# Esquematico.net
KiCad netlist of a schematic drawn in Altium Designer
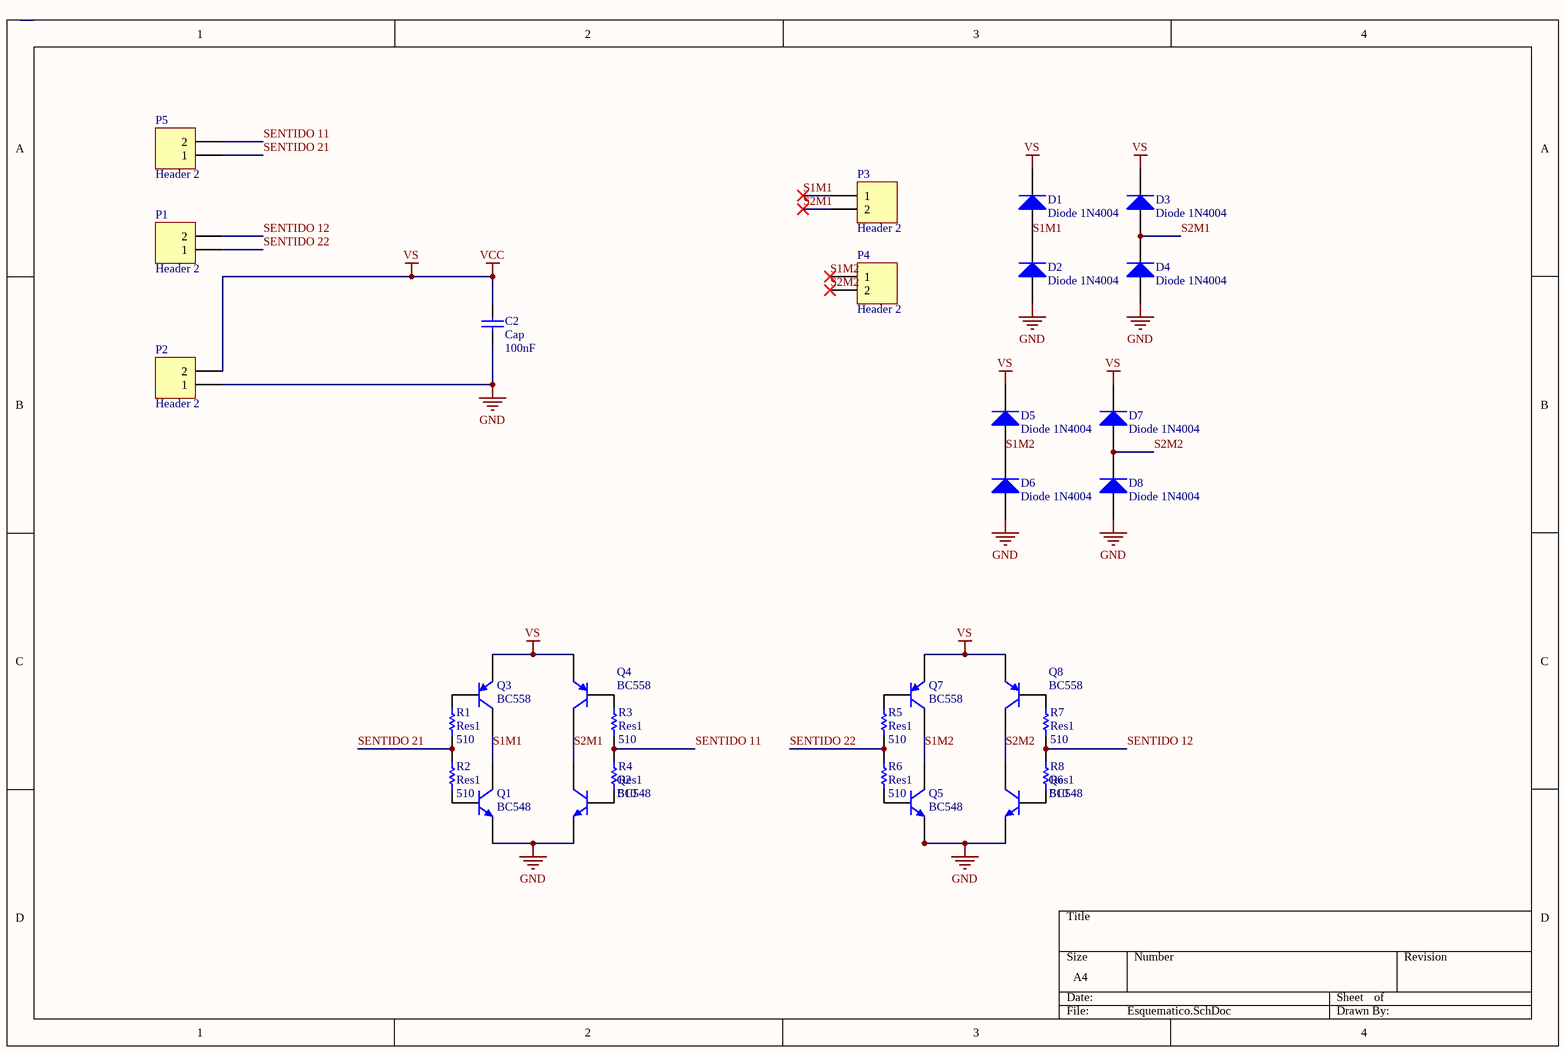
[diagram p0: Esquematico.SchDoc]

(export (version "E")
  (design (tool "Eeschema 10.0.6"))
  (components
    (comp (ref "C2")
      (value "Cap")
      (footprint "RAD-0.1")
      (description "Capacitor")
      (fields (field (name "ALTIUM_VALUE") "100nF") (field (name "PUBLISHER") "Altium Limited"))
      (libsource (lib "Miscellaneous Devices") (part "Cap"))
    )
    (comp (ref "D1")
      (value "Diode 1N4004")
      (footprint "DO-41")
      (description "1 Amp General Purpose Rectifier")
      (fields (field (name "PUBLISHER") "Altium Limited"))
      (libsource (lib "Miscellaneous Devices") (part "Diode 1N4004"))
    )
    (comp (ref "D2")
      (value "Diode 1N4004")
      (footprint "DO-41")
      (description "1 Amp General Purpose Rectifier")
      (fields (field (name "PUBLISHER") "Altium Limited"))
      (libsource (lib "Miscellaneous Devices") (part "Diode 1N4004"))
    )
    (comp (ref "D3")
      (value "Diode 1N4004")
      (footprint "DO-41")
      (description "1 Amp General Purpose Rectifier")
      (fields (field (name "PUBLISHER") "Altium Limited"))
      (libsource (lib "Miscellaneous Devices") (part "Diode 1N4004"))
    )
    (comp (ref "D4")
      (value "Diode 1N4004")
      (footprint "DO-41")
      (description "1 Amp General Purpose Rectifier")
      (fields (field (name "PUBLISHER") "Altium Limited"))
      (libsource (lib "Miscellaneous Devices") (part "Diode 1N4004"))
    )
    (comp (ref "D5")
      (value "Diode 1N4004")
      (footprint "DO-41")
      (description "1 Amp General Purpose Rectifier")
      (fields (field (name "PUBLISHER") "Altium Limited"))
      (libsource (lib "Miscellaneous Devices") (part "Diode 1N4004"))
    )
    (comp (ref "D6")
      (value "Diode 1N4004")
      (footprint "DO-41")
      (description "1 Amp General Purpose Rectifier")
      (fields (field (name "PUBLISHER") "Altium Limited"))
      (libsource (lib "Miscellaneous Devices") (part "Diode 1N4004"))
    )
    (comp (ref "D7")
      (value "Diode 1N4004")
      (footprint "DO-41")
      (description "1 Amp General Purpose Rectifier")
      (fields (field (name "PUBLISHER") "Altium Limited"))
      (libsource (lib "Miscellaneous Devices") (part "Diode 1N4004"))
    )
    (comp (ref "D8")
      (value "Diode 1N4004")
      (footprint "DO-41")
      (description "1 Amp General Purpose Rectifier")
      (fields (field (name "PUBLISHER") "Altium Limited"))
      (libsource (lib "Miscellaneous Devices") (part "Diode 1N4004"))
    )
    (comp (ref "P1")
      (value "Header 2")
      (footprint "HDR1X2")
      (description "Header, 2-Pin")
      (fields (field (name "PUBLISHER") "Altium Limited"))
      (libsource (lib "Miscellaneous Connectors") (part "Header 2"))
    )
    (comp (ref "P2")
      (value "Header 2")
      (footprint "HDR1X2")
      (description "Header, 2-Pin")
      (fields (field (name "PUBLISHER") "Altium Limited"))
      (libsource (lib "Miscellaneous Connectors") (part "Header 2"))
    )
    (comp (ref "P3")
      (value "Header 2")
      (footprint "HDR1X2")
      (description "Header, 2-Pin")
      (fields (field (name "PUBLISHER") "Altium Limited"))
      (libsource (lib "") (part "Header 2_1"))
    )
    (comp (ref "P4")
      (value "Header 2")
      (footprint "HDR1X2")
      (description "Header, 2-Pin")
      (fields (field (name "PUBLISHER") "Altium Limited"))
      (libsource (lib "") (part "Header 2_1"))
    )
    (comp (ref "P5")
      (value "Header 2")
      (footprint "HDR1X2")
      (description "Header, 2-Pin")
      (fields (field (name "PUBLISHER") "Altium Limited"))
      (libsource (lib "Miscellaneous Connectors") (part "Header 2"))
    )
    (comp (ref "Q1")
      (value "BC548")
      (footprint "TO-92")
      (description "NPN General Purpose Amplifier")
      (fields (field (name "PUBLISHER") "Altium Limited"))
      (libsource (lib "Components") (part "BC548"))
    )
    (comp (ref "Q2")
      (value "BC548")
      (footprint "TO-92")
      (description "NPN General Purpose Amplifier")
      (fields (field (name "PUBLISHER") "Altium Limited"))
      (libsource (lib "Components") (part "BC548"))
    )
    (comp (ref "Q3")
      (value "BC558")
      (footprint "TO-92")
      (description "PNP Bipolar Transistor")
      (fields (field (name "PUBLISHER") "Altium Limited"))
      (libsource (lib "Components") (part "BC558"))
    )
    (comp (ref "Q4")
      (value "BC558")
      (footprint "TO-92")
      (description "PNP Bipolar Transistor")
      (fields (field (name "PUBLISHER") "Altium Limited"))
      (libsource (lib "Components") (part "BC558"))
    )
    (comp (ref "Q5")
      (value "BC548")
      (footprint "TO-92")
      (description "NPN General Purpose Amplifier")
      (fields (field (name "PUBLISHER") "Altium Limited"))
      (libsource (lib "Components") (part "BC548"))
    )
    (comp (ref "Q6")
      (value "BC548")
      (footprint "TO-92")
      (description "NPN General Purpose Amplifier")
      (fields (field (name "PUBLISHER") "Altium Limited"))
      (libsource (lib "Components") (part "BC548"))
    )
    (comp (ref "Q7")
      (value "BC558")
      (footprint "TO-92")
      (description "PNP Bipolar Transistor")
      (fields (field (name "PUBLISHER") "Altium Limited"))
      (libsource (lib "Components") (part "BC558"))
    )
    (comp (ref "Q8")
      (value "BC558")
      (footprint "TO-92")
      (description "PNP Bipolar Transistor")
      (fields (field (name "PUBLISHER") "Altium Limited"))
      (libsource (lib "Components") (part "BC558"))
    )
    (comp (ref "R1")
      (value "Res1")
      (footprint "AXIAL-0.3")
      (description "Resistor")
      (fields (field (name "ALTIUM_VALUE") "510") (field (name "PUBLISHER") "Altium Limited"))
      (libsource (lib "Miscellaneous Devices") (part "Res1"))
    )
    (comp (ref "R2")
      (value "Res1")
      (footprint "AXIAL-0.3")
      (description "Resistor")
      (fields (field (name "ALTIUM_VALUE") "510") (field (name "PUBLISHER") "Altium Limited"))
      (libsource (lib "Miscellaneous Devices") (part "Res1"))
    )
    (comp (ref "R3")
      (value "Res1")
      (footprint "AXIAL-0.3")
      (description "Resistor")
      (fields (field (name "ALTIUM_VALUE") "510") (field (name "PUBLISHER") "Altium Limited"))
      (libsource (lib "Miscellaneous Devices") (part "Res1"))
    )
    (comp (ref "R4")
      (value "Res1")
      (footprint "AXIAL-0.3")
      (description "Resistor")
      (fields (field (name "ALTIUM_VALUE") "510") (field (name "PUBLISHER") "Altium Limited"))
      (libsource (lib "Miscellaneous Devices") (part "Res1"))
    )
    (comp (ref "R5")
      (value "Res1")
      (footprint "AXIAL-0.3")
      (description "Resistor")
      (fields (field (name "ALTIUM_VALUE") "510") (field (name "PUBLISHER") "Altium Limited"))
      (libsource (lib "Miscellaneous Devices") (part "Res1"))
    )
    (comp (ref "R6")
      (value "Res1")
      (footprint "AXIAL-0.3")
      (description "Resistor")
      (fields (field (name "ALTIUM_VALUE") "510") (field (name "PUBLISHER") "Altium Limited"))
      (libsource (lib "Miscellaneous Devices") (part "Res1"))
    )
    (comp (ref "R7")
      (value "Res1")
      (footprint "AXIAL-0.3")
      (description "Resistor")
      (fields (field (name "ALTIUM_VALUE") "510") (field (name "PUBLISHER") "Altium Limited"))
      (libsource (lib "Miscellaneous Devices") (part "Res1"))
    )
    (comp (ref "R8")
      (value "Res1")
      (footprint "AXIAL-0.3")
      (description "Resistor")
      (fields (field (name "ALTIUM_VALUE") "510") (field (name "PUBLISHER") "Altium Limited"))
      (libsource (lib "Miscellaneous Devices") (part "Res1"))
    )
  )
  (nets
    (net (code "1") (name "/S1M1") (class "Default")
      (node (ref "D1") (pin "1") (pinfunction "A_1") (pintype "passive"))
      (node (ref "D2") (pin "2") (pinfunction "K_2") (pintype "passive"))
      (node (ref "P3") (pin "1") (pinfunction "1_1") (pintype "passive"))
      (node (ref "Q1") (pin "3") (pinfunction "C_3") (pintype "passive"))
      (node (ref "Q3") (pin "3") (pinfunction "C_3") (pintype "passive"))
    )
    (net (code "2") (name "/S1M2") (class "Default")
      (node (ref "D5") (pin "1") (pinfunction "A_1") (pintype "passive"))
      (node (ref "D6") (pin "2") (pinfunction "K_2") (pintype "passive"))
      (node (ref "P4") (pin "1") (pinfunction "1_1") (pintype "passive"))
      (node (ref "Q5") (pin "3") (pinfunction "C_3") (pintype "passive"))
      (node (ref "Q7") (pin "3") (pinfunction "C_3") (pintype "passive"))
    )
    (net (code "3") (name "/S2M1") (class "Default")
      (node (ref "D3") (pin "1") (pinfunction "A_1") (pintype "passive"))
      (node (ref "D4") (pin "2") (pinfunction "K_2") (pintype "passive"))
      (node (ref "P3") (pin "2") (pinfunction "2_2") (pintype "passive"))
      (node (ref "Q2") (pin "3") (pinfunction "C_3") (pintype "passive"))
      (node (ref "Q4") (pin "3") (pinfunction "C_3") (pintype "passive"))
    )
    (net (code "4") (name "/S2M2") (class "Default")
      (node (ref "D7") (pin "1") (pinfunction "A_1") (pintype "passive"))
      (node (ref "D8") (pin "2") (pinfunction "K_2") (pintype "passive"))
      (node (ref "P4") (pin "2") (pinfunction "2_2") (pintype "passive"))
      (node (ref "Q6") (pin "3") (pinfunction "C_3") (pintype "passive"))
      (node (ref "Q8") (pin "3") (pinfunction "C_3") (pintype "passive"))
    )
    (net (code "5") (name "/SENTIDO 11") (class "Default")
      (node (ref "P5") (pin "2") (pinfunction "2_2") (pintype "passive"))
      (node (ref "R3") (pin "1") (pinfunction "1_1") (pintype "passive"))
      (node (ref "R4") (pin "2") (pinfunction "2_2") (pintype "passive"))
    )
    (net (code "6") (name "/SENTIDO 12") (class "Default")
      (node (ref "P1") (pin "2") (pinfunction "2_2") (pintype "passive"))
      (node (ref "R7") (pin "1") (pinfunction "1_1") (pintype "passive"))
      (node (ref "R8") (pin "2") (pinfunction "2_2") (pintype "passive"))
    )
    (net (code "7") (name "/SENTIDO 21") (class "Default")
      (node (ref "P5") (pin "1") (pinfunction "1_1") (pintype "passive"))
      (node (ref "R1") (pin "1") (pinfunction "1_1") (pintype "passive"))
      (node (ref "R2") (pin "2") (pinfunction "2_2") (pintype "passive"))
    )
    (net (code "8") (name "/SENTIDO 22") (class "Default")
      (node (ref "P1") (pin "1") (pinfunction "1_1") (pintype "passive"))
      (node (ref "R5") (pin "1") (pinfunction "1_1") (pintype "passive"))
      (node (ref "R6") (pin "2") (pinfunction "2_2") (pintype "passive"))
    )
    (net (code "9") (name "GND") (class "Default")
      (node (ref "C2") (pin "1") (pinfunction "1_1") (pintype "passive"))
      (node (ref "D2") (pin "1") (pinfunction "A_1") (pintype "passive"))
      (node (ref "D4") (pin "1") (pinfunction "A_1") (pintype "passive"))
      (node (ref "D6") (pin "1") (pinfunction "A_1") (pintype "passive"))
      (node (ref "D8") (pin "1") (pinfunction "A_1") (pintype "passive"))
      (node (ref "P2") (pin "1") (pinfunction "1_1") (pintype "passive"))
      (node (ref "Q1") (pin "1") (pinfunction "E_1") (pintype "passive"))
      (node (ref "Q2") (pin "1") (pinfunction "E_1") (pintype "passive"))
      (node (ref "Q5") (pin "1") (pinfunction "E_1") (pintype "passive"))
      (node (ref "Q6") (pin "1") (pinfunction "E_1") (pintype "passive"))
    )
    (net (code "10") (name "Net-(Q1-B)") (class "Default")
      (node (ref "Q1") (pin "2") (pinfunction "B_2") (pintype "passive"))
      (node (ref "R2") (pin "1") (pinfunction "1_1") (pintype "passive"))
    )
    (net (code "11") (name "Net-(Q2-B)") (class "Default")
      (node (ref "Q2") (pin "2") (pinfunction "B_2") (pintype "passive"))
      (node (ref "R4") (pin "1") (pinfunction "1_1") (pintype "passive"))
    )
    (net (code "12") (name "Net-(Q3-B)") (class "Default")
      (node (ref "Q3") (pin "2") (pinfunction "B_2") (pintype "passive"))
      (node (ref "R1") (pin "2") (pinfunction "2_2") (pintype "passive"))
    )
    (net (code "13") (name "Net-(Q4-B)") (class "Default")
      (node (ref "Q4") (pin "2") (pinfunction "B_2") (pintype "passive"))
      (node (ref "R3") (pin "2") (pinfunction "2_2") (pintype "passive"))
    )
    (net (code "14") (name "Net-(Q5-B)") (class "Default")
      (node (ref "Q5") (pin "2") (pinfunction "B_2") (pintype "passive"))
      (node (ref "R6") (pin "1") (pinfunction "1_1") (pintype "passive"))
    )
    (net (code "15") (name "Net-(Q6-B)") (class "Default")
      (node (ref "Q6") (pin "2") (pinfunction "B_2") (pintype "passive"))
      (node (ref "R8") (pin "1") (pinfunction "1_1") (pintype "passive"))
    )
    (net (code "16") (name "Net-(Q7-B)") (class "Default")
      (node (ref "Q7") (pin "2") (pinfunction "B_2") (pintype "passive"))
      (node (ref "R5") (pin "2") (pinfunction "2_2") (pintype "passive"))
    )
    (net (code "17") (name "Net-(Q8-B)") (class "Default")
      (node (ref "Q8") (pin "2") (pinfunction "B_2") (pintype "passive"))
      (node (ref "R7") (pin "2") (pinfunction "2_2") (pintype "passive"))
    )
    (net (code "18") (name "VCC") (class "Default")
      (node (ref "C2") (pin "2") (pinfunction "2_2") (pintype "passive"))
      (node (ref "D1") (pin "2") (pinfunction "K_2") (pintype "passive"))
      (node (ref "D3") (pin "2") (pinfunction "K_2") (pintype "passive"))
      (node (ref "D5") (pin "2") (pinfunction "K_2") (pintype "passive"))
      (node (ref "D7") (pin "2") (pinfunction "K_2") (pintype "passive"))
      (node (ref "P2") (pin "2") (pinfunction "2_2") (pintype "passive"))
      (node (ref "Q3") (pin "1") (pinfunction "E_1") (pintype "passive"))
      (node (ref "Q4") (pin "1") (pinfunction "E_1") (pintype "passive"))
      (node (ref "Q7") (pin "1") (pinfunction "E_1") (pintype "passive"))
      (node (ref "Q8") (pin "1") (pinfunction "E_1") (pintype "passive"))
    )
  )
)
